# FastCharge.net
KiCad netlist of a schematic drawn in Altium Designer
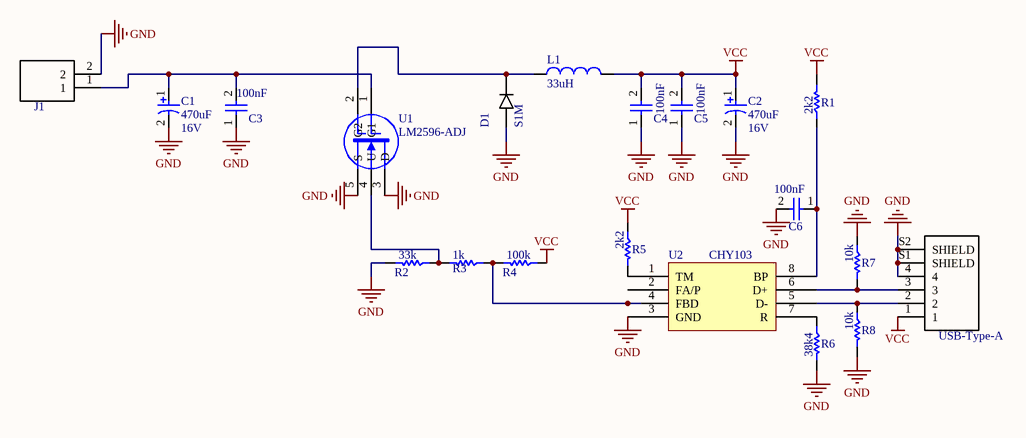
[diagram p0: FastCharge.SchDoc]

(export (version "E")
  (design (tool "Eeschema 10.0.6"))
  (components
    (comp (ref "C1")
      (value "470uF")
      (footprint "RB5-10.5")
      (fields (field (name "ALTIUM_UNNAMED_8") "16V"))
      (libsource (lib "3D LIB") (part "CAP"))
    )
    (comp (ref "C2")
      (value "470uF")
      (footprint "RB5-10.5")
      (fields (field (name "ALTIUM_UNNAMED_8") "16V"))
      (libsource (lib "3D LIB") (part "CAP"))
    )
    (comp (ref "C3") (value "100nF") (footprint "6-0805_L") (libsource (lib "3D LIB") (part "CAP NON")))
    (comp (ref "C4") (value "100nF") (footprint "6-0805_L") (libsource (lib "3D LIB") (part "CAP NON")))
    (comp (ref "C5") (value "100nF") (footprint "6-0805_L") (libsource (lib "3D LIB") (part "CAP NON")))
    (comp (ref "C6") (value "100nF") (footprint "6-0805_L") (libsource (lib "3D LIB") (part "CAP NON")))
    (comp (ref "D1")
      (value "S1M")
      (footprint "*DIOM5227X270N_S1M(Primary)")
      (description "S1 Series 1000 V 1 A 1 uA Surface Mount General Purpose Rectifier - DO-214AC")
      (fields (field (name "MF") "ON Semiconductor"))
      (libsource (lib "S1M") (part "S1M"))
    )
    (comp (ref "J1")
      (value "6-1123723-2")
      (footprint "*TE_6-1123723-2")
      (description "3.96 EP HDR ASSY 2P_GREEN_")
      (fields (field (name "MF") "TE Connectivity"))
      (libsource (lib "6-1123723-2") (part "6-1123723-2"))
    )
    (comp (ref "L1")
      (value "33uH")
      (footprint "IND_SMD-13.0mm")
      (description "Inductor")
      (libsource (lib "3D LIB") (part "Inductor"))
    )
    (comp (ref "R1") (value "2k2") (footprint "6-0805_L") (libsource (lib "3D LIB") (part "RESISTOR")))
    (comp (ref "R2") (value "33k") (footprint "6-0805_L") (libsource (lib "3D LIB") (part "RESISTOR")))
    (comp (ref "R3") (value "1k") (footprint "6-0805_L") (libsource (lib "3D LIB") (part "RESISTOR")))
    (comp (ref "R4") (value "100k") (footprint "6-0805_L") (libsource (lib "3D LIB") (part "RESISTOR")))
    (comp (ref "R5") (value "2k2") (footprint "6-0805_L") (libsource (lib "3D LIB") (part "RESISTOR")))
    (comp (ref "R6") (value "38k4") (footprint "6-0805_L") (libsource (lib "3D LIB") (part "RESISTOR")))
    (comp (ref "R7") (value "10k") (footprint "6-0805_L") (libsource (lib "3D LIB") (part "RESISTOR")))
    (comp (ref "R8") (value "10k") (footprint "6-0805_L") (libsource (lib "3D LIB") (part "RESISTOR")))
    (comp (ref "U1")
      (value "LM2596-ADJ")
      (footprint "T05A")
      (description "Two-Gate, N-Channel MOSFET, Externally Terminated Substrate")
      (fields (field (name "PUBLISHER") "Altium Limited"))
      (libsource (lib "Miscellaneous Devices") (part "MOSFET-N3"))
    )
    (comp (ref "U2") (value "CHY103") (footprint "8 pin SOIC_L") (libsource (lib "Schlib") (part "CHY103")))
    (comp (ref "USB-Type-A")
      (value "1-292303-1")
      (footprint "*TE_1-292303-1_1-292303-1(Primary)")
      (description "Conn USB 2.0 Type A RCP 4 POS Solder RA SMD 4 Terminal 1 Port Box/Tray")
      (fields (field (name "MF") "TE Connectivity"))
      (libsource (lib "USB-TYPE-A") (part "1-292303-1"))
    )
  )
  (nets
    (net (code "1") (name "GND") (class "Default")
      (node (ref "C1") (pin "2") (pinfunction "2_2") (pintype "passive"))
      (node (ref "C2") (pin "2") (pinfunction "2_2") (pintype "passive"))
      (node (ref "C3") (pin "1") (pinfunction "1_1") (pintype "passive"))
      (node (ref "C4") (pin "1") (pinfunction "1_1") (pintype "passive"))
      (node (ref "C5") (pin "1") (pinfunction "1_1") (pintype "passive"))
      (node (ref "C6") (pin "2") (pinfunction "2_2") (pintype "passive"))
      (node (ref "D1") (pin "A") (pinfunction "A_A") (pintype "passive"))
      (node (ref "J1") (pin "2") (pinfunction "2_2") (pintype "passive"))
      (node (ref "R2") (pin "2") (pinfunction "2_2") (pintype "passive"))
      (node (ref "R6") (pin "2") (pinfunction "2_2") (pintype "passive"))
      (node (ref "R7") (pin "1") (pinfunction "1_1") (pintype "passive"))
      (node (ref "R8") (pin "2") (pinfunction "2_2") (pintype "passive"))
      (node (ref "U1") (pin "3") (pinfunction "D_3") (pintype "passive"))
      (node (ref "U1") (pin "5") (pinfunction "S_5") (pintype "passive"))
      (node (ref "U2") (pin "3") (pinfunction "GND_3") (pintype "passive"))
      (node (ref "USB-Type-A") (pin "4") (pinfunction "4_4") (pintype "passive"))
      (node (ref "USB-Type-A") (pin "S1") (pinfunction "SHIELD_S1") (pintype "passive"))
      (node (ref "USB-Type-A") (pin "S2") (pinfunction "SHIELD_S2") (pintype "passive"))
    )
    (net (code "2") (name "Net-(D1-K)") (class "Default")
      (node (ref "D1") (pin "C") (pinfunction "K_C") (pintype "passive"))
      (node (ref "L1") (pin "1") (pinfunction "1_1") (pintype "passive"))
      (node (ref "U1") (pin "2") (pinfunction "G2_2") (pintype "passive"))
    )
    (net (code "3") (name "Net-(U1-G1)") (class "Default")
      (node (ref "C1") (pin "1") (pinfunction "1_1") (pintype "passive"))
      (node (ref "C3") (pin "2") (pinfunction "2_2") (pintype "passive"))
      (node (ref "J1") (pin "1") (pinfunction "1_1") (pintype "passive"))
      (node (ref "U1") (pin "1") (pinfunction "G1_1") (pintype "passive"))
    )
    (net (code "4") (name "Net-(U1-U)") (class "Default")
      (node (ref "R2") (pin "1") (pinfunction "1_1") (pintype "passive"))
      (node (ref "R3") (pin "2") (pinfunction "2_2") (pintype "passive"))
      (node (ref "U1") (pin "4") (pinfunction "U_4") (pintype "passive"))
    )
    (net (code "5") (name "Net-(U2-BP)") (class "Default")
      (node (ref "C6") (pin "1") (pinfunction "1_1") (pintype "passive"))
      (node (ref "R1") (pin "1") (pinfunction "1_1") (pintype "passive"))
      (node (ref "U2") (pin "8") (pinfunction "BP_8") (pintype "passive"))
    )
    (net (code "6") (name "Net-(U2-D+)") (class "Default")
      (node (ref "R7") (pin "2") (pinfunction "2_2") (pintype "passive"))
      (node (ref "U2") (pin "6") (pinfunction "D+_6") (pintype "passive"))
      (node (ref "USB-Type-A") (pin "3") (pinfunction "3_3") (pintype "passive"))
    )
    (net (code "7") (name "Net-(U2-D-)") (class "Default")
      (node (ref "R8") (pin "1") (pinfunction "1_1") (pintype "passive"))
      (node (ref "U2") (pin "5") (pinfunction "D-_5") (pintype "passive"))
      (node (ref "USB-Type-A") (pin "2") (pinfunction "2_2") (pintype "passive"))
    )
    (net (code "8") (name "Net-(U2-FBD)") (class "Default")
      (node (ref "R3") (pin "1") (pinfunction "1_1") (pintype "passive"))
      (node (ref "R4") (pin "2") (pinfunction "2_2") (pintype "passive"))
      (node (ref "U2") (pin "4") (pinfunction "FBD_4") (pintype "passive"))
    )
    (net (code "9") (name "Net-(U2-R)") (class "Default")
      (node (ref "R6") (pin "1") (pinfunction "1_1") (pintype "passive"))
      (node (ref "U2") (pin "7") (pinfunction "R_7") (pintype "passive"))
    )
    (net (code "10") (name "Net-(U2-TM)") (class "Default")
      (node (ref "R5") (pin "2") (pinfunction "2_2") (pintype "passive"))
      (node (ref "U2") (pin "1") (pinfunction "TM_1") (pintype "passive"))
    )
    (net (code "11") (name "VCC") (class "Default")
      (node (ref "C2") (pin "1") (pinfunction "1_1") (pintype "passive"))
      (node (ref "C4") (pin "2") (pinfunction "2_2") (pintype "passive"))
      (node (ref "C5") (pin "2") (pinfunction "2_2") (pintype "passive"))
      (node (ref "L1") (pin "2") (pinfunction "2_2") (pintype "passive"))
      (node (ref "R1") (pin "2") (pinfunction "2_2") (pintype "passive"))
      (node (ref "R4") (pin "1") (pinfunction "1_1") (pintype "passive"))
      (node (ref "R5") (pin "1") (pinfunction "1_1") (pintype "passive"))
      (node (ref "USB-Type-A") (pin "1") (pinfunction "1_1") (pintype "passive"))
    )
    (net (code "12") (name "unconnected-(U2-FA{slash}P-Pad2)") (class "Default")
      (node (ref "U2") (pin "2") (pinfunction "FA/P_2") (pintype "passive"))
    )
  )
)
